# FT232.net
KiCad netlist of a schematic drawn in Altium Designer
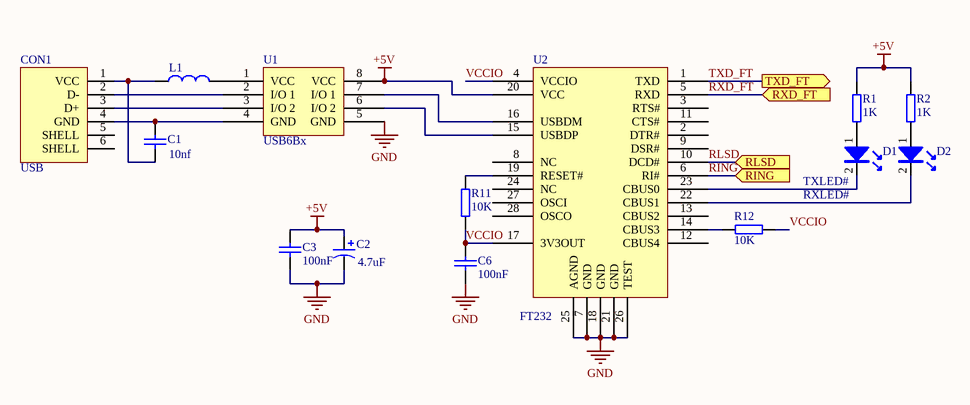
[diagram p0: FT232.SchDoc]

(export (version "E")
  (design (tool "Eeschema 10.0.6"))
  (components
    (comp (ref "C1")
      (value "10nf")
      (footprint "C0603")
      (description "Capacitor")
      (fields (field (name "Comment") "CAP"))
      (libsource (lib "PV") (part "CAP"))
    )
    (comp (ref "C2")
      (value "4.7uF")
      (footprint "T3528")
      (fields (field (name "Comment") "CAP+"))
      (libsource (lib "PV") (part "CAP+"))
    )
    (comp (ref "C3")
      (value "100nF")
      (footprint "C0603")
      (description "Capacitor")
      (fields (field (name "Comment") "CAP"))
      (libsource (lib "PV") (part "CAP"))
    )
    (comp (ref "C6")
      (value "100nF")
      (footprint "C0603")
      (description "Capacitor")
      (fields (field (name "Comment") "CAP"))
      (libsource (lib "PV") (part "CAP"))
    )
    (comp (ref "CON1") (value "USB") (footprint "USB2.5-2H4D") (libsource (lib "连接器_电缆组件_插座") (part "USB")))
    (comp (ref "D1") (value "LED") (footprint "D0805") (libsource (lib "PV") (part "LED")))
    (comp (ref "D2") (value "LED") (footprint "D0805") (libsource (lib "PV") (part "LED")))
    (comp (ref "L1") (value "INDUCTOR") (footprint "L0805") (libsource (lib "PV") (part "INDUCTOR")))
    (comp (ref "R1")
      (value "1K")
      (footprint "R0603")
      (fields (field (name "Comment") "res"))
      (libsource (lib "PV") (part "RES"))
    )
    (comp (ref "R2")
      (value "1K")
      (footprint "R0603")
      (fields (field (name "Comment") "res"))
      (libsource (lib "PV") (part "RES"))
    )
    (comp (ref "R11")
      (value "10K")
      (footprint "R0603")
      (fields (field (name "Comment") "res"))
      (libsource (lib "PV") (part "RES"))
    )
    (comp (ref "R12")
      (value "10K")
      (footprint "R0603")
      (fields (field (name "Comment") "res"))
      (libsource (lib "PV") (part "RES"))
    )
    (comp (ref "U1") (value "USB6Bx") (footprint "SO8") (libsource (lib "Schlib1") (part "USB6Bx")))
    (comp (ref "U2") (value "FT232") (footprint "SSOP-28") (libsource (lib "Schlib1") (part "FT232")))
  )
  (nets
    (net (code "1") (name "+5V") (class "Default")
      (node (ref "C2") (pin "1") (pinfunction "1_1") (pintype "passive"))
      (node (ref "C3") (pin "2") (pinfunction "2_2") (pintype "passive"))
      (node (ref "R1") (pin "2") (pinfunction "2_2") (pintype "passive"))
      (node (ref "R2") (pin "2") (pinfunction "2_2") (pintype "passive"))
      (node (ref "U1") (pin "8") (pinfunction "VCC_8") (pintype "passive"))
      (node (ref "U2") (pin "20") (pinfunction "VCC_20") (pintype "passive"))
    )
    (net (code "2") (name "/RING") (class "Default")
      (node (ref "U2") (pin "6") (pinfunction "RI#_6") (pintype "passive"))
    )
    (net (code "3") (name "/RLSD") (class "Default")
      (node (ref "U2") (pin "10") (pinfunction "DCD#_10") (pintype "passive"))
    )
    (net (code "4") (name "/RXD_FT") (class "Default")
      (node (ref "U2") (pin "5") (pinfunction "RXD_5") (pintype "passive"))
    )
    (net (code "5") (name "/TXD_FT") (class "Default")
      (node (ref "U2") (pin "1") (pinfunction "TXD_1") (pintype "passive"))
    )
    (net (code "6") (name "/VCCIO") (class "Default")
      (node (ref "C6") (pin "2") (pinfunction "2_2") (pintype "passive"))
      (node (ref "R11") (pin "2") (pinfunction "2_2") (pintype "passive"))
      (node (ref "R12") (pin "1") (pinfunction "1_1") (pintype "passive"))
      (node (ref "U2") (pin "17") (pinfunction "3V3OUT_17") (pintype "passive"))
      (node (ref "U2") (pin "4") (pinfunction "VCCIO_4") (pintype "passive"))
    )
    (net (code "7") (name "GND") (class "Default")
      (node (ref "C2") (pin "2") (pinfunction "2_2") (pintype "passive"))
      (node (ref "C3") (pin "1") (pinfunction "1_1") (pintype "passive"))
      (node (ref "C6") (pin "1") (pinfunction "1_1") (pintype "passive"))
      (node (ref "U1") (pin "5") (pinfunction "GND_5") (pintype "passive"))
      (node (ref "U2") (pin "18") (pinfunction "GND_18") (pintype "passive"))
      (node (ref "U2") (pin "21") (pinfunction "GND_21") (pintype "passive"))
      (node (ref "U2") (pin "25") (pinfunction "AGND_25") (pintype "passive"))
      (node (ref "U2") (pin "26") (pinfunction "TEST_26") (pintype "passive"))
      (node (ref "U2") (pin "7") (pinfunction "GND_7") (pintype "passive"))
    )
    (net (code "8") (name "Net-(CON1-D+)") (class "Default")
      (node (ref "CON1") (pin "3") (pinfunction "D+_3") (pintype "passive"))
      (node (ref "U1") (pin "3") (pinfunction "I/O_2_3") (pintype "passive"))
    )
    (net (code "9") (name "Net-(CON1-D-)") (class "Default")
      (node (ref "CON1") (pin "2") (pinfunction "D-_2") (pintype "passive"))
      (node (ref "U1") (pin "2") (pinfunction "I/O_1_2") (pintype "passive"))
    )
    (net (code "10") (name "Net-(CON1-GND)") (class "Default")
      (node (ref "C1") (pin "2") (pinfunction "2_2") (pintype "passive"))
      (node (ref "CON1") (pin "4") (pinfunction "GND_4") (pintype "passive"))
      (node (ref "U1") (pin "4") (pinfunction "GND_4") (pintype "passive"))
    )
    (net (code "11") (name "Net-(CON1-VCC)") (class "Default")
      (node (ref "C1") (pin "1") (pinfunction "1_1") (pintype "passive"))
      (node (ref "CON1") (pin "1") (pinfunction "VCC_1") (pintype "passive"))
      (node (ref "L1") (pin "1") (pinfunction "1_1") (pintype "passive"))
    )
    (net (code "12") (name "Net-(D1-Pad1)") (class "Default")
      (node (ref "D1") (pin "1") (pinfunction "1_1") (pintype "passive"))
      (node (ref "R1") (pin "1") (pinfunction "1_1") (pintype "passive"))
    )
    (net (code "13") (name "Net-(D2-Pad1)") (class "Default")
      (node (ref "D2") (pin "1") (pinfunction "1_1") (pintype "passive"))
      (node (ref "R2") (pin "1") (pinfunction "1_1") (pintype "passive"))
    )
    (net (code "14") (name "Net-(L1-Pad2)") (class "Default")
      (node (ref "L1") (pin "2") (pinfunction "2_2") (pintype "passive"))
      (node (ref "U1") (pin "1") (pinfunction "VCC_1") (pintype "passive"))
    )
    (net (code "15") (name "Net-(U2-CBUS0)") (class "Default")
      (node (ref "D1") (pin "2") (pinfunction "2_2") (pintype "passive"))
      (node (ref "U2") (pin "23") (pinfunction "CBUS0_23") (pintype "passive"))
    )
    (net (code "16") (name "Net-(U2-CBUS1)") (class "Default")
      (node (ref "D2") (pin "2") (pinfunction "2_2") (pintype "passive"))
      (node (ref "U2") (pin "22") (pinfunction "CBUS1_22") (pintype "passive"))
    )
    (net (code "17") (name "Net-(U2-CBUS3)") (class "Default")
      (node (ref "R12") (pin "2") (pinfunction "2_2") (pintype "passive"))
      (node (ref "U2") (pin "14") (pinfunction "CBUS3_14") (pintype "passive"))
    )
    (net (code "18") (name "Net-(U2-RESET#)") (class "Default")
      (node (ref "R11") (pin "1") (pinfunction "1_1") (pintype "passive"))
      (node (ref "U2") (pin "19") (pinfunction "RESET#_19") (pintype "passive"))
    )
    (net (code "19") (name "Net-(U2-USBDM)") (class "Default")
      (node (ref "U1") (pin "7") (pinfunction "I/O_1_7") (pintype "passive"))
      (node (ref "U2") (pin "16") (pinfunction "USBDM_16") (pintype "passive"))
    )
    (net (code "20") (name "Net-(U2-USBDP)") (class "Default")
      (node (ref "U1") (pin "6") (pinfunction "I/O_2_6") (pintype "passive"))
      (node (ref "U2") (pin "15") (pinfunction "USBDP_15") (pintype "passive"))
    )
    (net (code "21") (name "unconnected-(CON1-SHELL-Pad5)") (class "Default")
      (node (ref "CON1") (pin "5") (pinfunction "SHELL_5") (pintype "passive"))
    )
    (net (code "22") (name "unconnected-(CON1-SHELL-Pad6)") (class "Default")
      (node (ref "CON1") (pin "6") (pinfunction "SHELL_6") (pintype "passive"))
    )
    (net (code "23") (name "unconnected-(U2-CBUS2-Pad13)") (class "Default")
      (node (ref "U2") (pin "13") (pinfunction "CBUS2_13") (pintype "passive"))
    )
    (net (code "24") (name "unconnected-(U2-CBUS4-Pad12)") (class "Default")
      (node (ref "U2") (pin "12") (pinfunction "CBUS4_12") (pintype "passive"))
    )
    (net (code "25") (name "unconnected-(U2-CTS#-Pad11)") (class "Default")
      (node (ref "U2") (pin "11") (pinfunction "CTS#_11") (pintype "passive"))
    )
    (net (code "26") (name "unconnected-(U2-DSR#-Pad9)") (class "Default")
      (node (ref "U2") (pin "9") (pinfunction "DSR#_9") (pintype "passive"))
    )
    (net (code "27") (name "unconnected-(U2-DTR#-Pad2)") (class "Default")
      (node (ref "U2") (pin "2") (pinfunction "DTR#_2") (pintype "passive"))
    )
    (net (code "28") (name "unconnected-(U2-NC-Pad8)") (class "Default")
      (node (ref "U2") (pin "8") (pinfunction "NC_8") (pintype "passive"))
    )
    (net (code "29") (name "unconnected-(U2-NC-Pad24)") (class "Default")
      (node (ref "U2") (pin "24") (pinfunction "NC_24") (pintype "passive"))
    )
    (net (code "30") (name "unconnected-(U2-OSCI-Pad27)") (class "Default")
      (node (ref "U2") (pin "27") (pinfunction "OSCI_27") (pintype "passive"))
    )
    (net (code "31") (name "unconnected-(U2-OSCO-Pad28)") (class "Default")
      (node (ref "U2") (pin "28") (pinfunction "OSCO_28") (pintype "passive"))
    )
    (net (code "32") (name "unconnected-(U2-RTS#-Pad3)") (class "Default")
      (node (ref "U2") (pin "3") (pinfunction "RTS#_3") (pintype "passive"))
    )
  )
)
